# SmartSwitchBoard-2x2LK.net
KiCad netlist of a schematic drawn in EAGLE
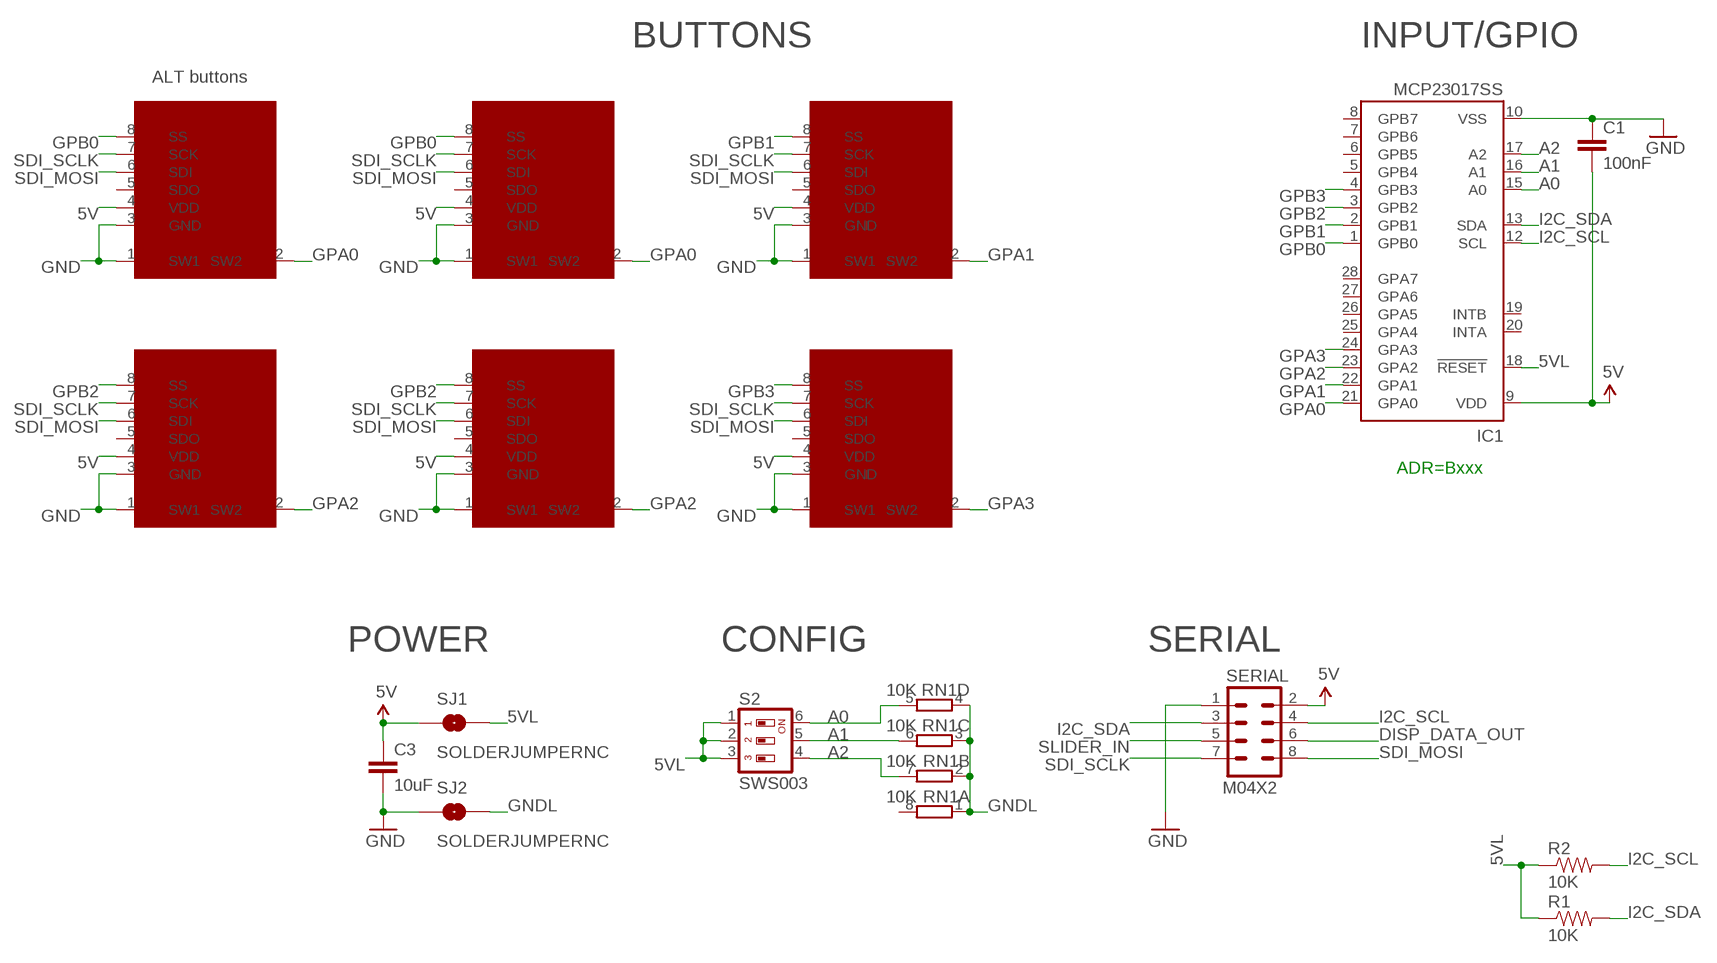
[diagram p0: schematic, sheet 1]

(export (version "E")
  (design (tool "Eeschema 10.0.6"))
  (components
    (comp (ref "C1")
      (value "100nF")
      (footprint "eagle-import:0603-CAP")
      (libsource (lib "eagle-import") (part "CAP0603-CAP"))
    )
    (comp (ref "C3")
      (value "10uF")
      (footprint "eagle-import:0805")
      (libsource (lib "eagle-import") (part "CAP0805"))
    )
    (comp (ref "IC1")
      (value "MCP23017SS")
      (footprint "eagle-import:SSOP28")
      (fields
        (field (name "MF") "MICROCHIP")
        (field (name "MPN") "MCP23017-E/SS")
        (field (name "MPN_1") "MCP23017-E/SS")
        (field (name "OC_FARNELL") "1467674")
        (field (name "OC_NEWARK") "31K2960")
      )
      (libsource (lib "eagle-import") (part "MCP23017SS"))
    )
    (comp (ref "R1")
      (value "10K")
      (footprint "eagle-import:0603-RES")
      (libsource (lib "eagle-import") (part "RESISTOR0603-RES"))
    )
    (comp (ref "R2")
      (value "10K")
      (footprint "eagle-import:0603-RES")
      (libsource (lib "eagle-import") (part "RESISTOR0603-RES"))
    )
    (comp (ref "RN1")
      (value "10K")
      (footprint "eagle-import:CAY16_HAND")
      (libsource (lib "eagle-import") (part "4R-NCAY16"))
    )
    (comp (ref "S2")
      (value "SWS003")
      (footprint "eagle-import:SMS-003")
      (libsource (lib "eagle-import") (part "SWS003"))
    )
    (comp (ref "SERIAL")
      (value "M04X2")
      (footprint "eagle-import:2X4")
      (libsource (lib "eagle-import") (part "M04X2"))
    )
    (comp (ref "SJ1")
      (value "SOLDERJUMPERNC")
      (footprint "eagle-import:SJ_2S")
      (libsource (lib "eagle-import") (part "SOLDERJUMPERNC"))
    )
    (comp (ref "SJ2")
      (value "SOLDERJUMPERNC")
      (footprint "eagle-import:SJ_2S")
      (libsource (lib "eagle-import") (part "SOLDERJUMPERNC"))
    )
    (comp (ref "U$2")
      (value "SMART_SWITCHSMART_SWITCH_8PIN")
      (footprint "eagle-import:SMART_SWITCH")
      (libsource (lib "eagle-import") (part "SMART_SWITCHSMART_SWITCH_8PIN"))
    )
    (comp (ref "U$3")
      (value "SMART_SWITCHSMART_SWITCH_8PIN")
      (footprint "eagle-import:SMART_SWITCH")
      (libsource (lib "eagle-import") (part "SMART_SWITCHSMART_SWITCH_8PIN"))
    )
    (comp (ref "U$4")
      (value "SMART_SWITCHSMART_SWITCH_8PIN")
      (footprint "eagle-import:SMART_SWITCH")
      (libsource (lib "eagle-import") (part "SMART_SWITCHSMART_SWITCH_8PIN"))
    )
    (comp (ref "U$5")
      (value "SMART_SWITCHSMART_SWITCH_8PIN")
      (footprint "eagle-import:SMART_SWITCH")
      (libsource (lib "eagle-import") (part "SMART_SWITCHSMART_SWITCH_8PIN"))
    )
    (comp (ref "U$6")
      (value "SMART_SWITCHSMART_SWITCH_8PIN")
      (footprint "eagle-import:SMART_SWITCH")
      (libsource (lib "eagle-import") (part "SMART_SWITCHSMART_SWITCH_8PIN"))
    )
    (comp (ref "U$7")
      (value "SMART_SWITCHSMART_SWITCH_8PIN")
      (footprint "eagle-import:SMART_SWITCH")
      (libsource (lib "eagle-import") (part "SMART_SWITCHSMART_SWITCH_8PIN"))
    )
  )
  (nets
    (net (code "1") (name "/5VL") (class "Default")
      (node (ref "IC1") (pin "18") (pinfunction "~{RESET}_18") (pintype "input"))
      (node (ref "R1") (pin "1") (pinfunction "1_1") (pintype "passive"))
      (node (ref "R2") (pin "1") (pinfunction "1_1") (pintype "passive"))
      (node (ref "S2") (pin "1") (pinfunction "1_1") (pintype "passive"))
      (node (ref "S2") (pin "2") (pinfunction "2_2") (pintype "passive"))
      (node (ref "S2") (pin "3") (pinfunction "3_3") (pintype "passive"))
      (node (ref "SJ1") (pin "2") (pinfunction "2_2") (pintype "passive"))
    )
    (net (code "2") (name "/A0") (class "Default")
      (node (ref "IC1") (pin "15") (pinfunction "A0_15") (pintype "input"))
      (node (ref "RN1") (pin "5") (pinfunction "2_5") (pintype "passive"))
      (node (ref "S2") (pin "6") (pinfunction "6_6") (pintype "passive"))
    )
    (net (code "3") (name "/A1") (class "Default")
      (node (ref "IC1") (pin "16") (pinfunction "A1_16") (pintype "input"))
      (node (ref "RN1") (pin "6") (pinfunction "2_6") (pintype "passive"))
      (node (ref "S2") (pin "5") (pinfunction "5_5") (pintype "passive"))
    )
    (net (code "4") (name "/A2") (class "Default")
      (node (ref "IC1") (pin "17") (pinfunction "A2_17") (pintype "input"))
      (node (ref "RN1") (pin "7") (pinfunction "2_7") (pintype "passive"))
      (node (ref "S2") (pin "4") (pinfunction "4_4") (pintype "passive"))
    )
    (net (code "5") (name "/DISP_DATA_OUT") (class "Default")
      (node (ref "SERIAL") (pin "6") (pinfunction "6_6") (pintype "passive"))
    )
    (net (code "6") (name "/GNDL") (class "Default")
      (node (ref "RN1") (pin "1") (pinfunction "1_1") (pintype "passive"))
      (node (ref "RN1") (pin "2") (pinfunction "1_2") (pintype "passive"))
      (node (ref "RN1") (pin "3") (pinfunction "1_3") (pintype "passive"))
      (node (ref "RN1") (pin "4") (pinfunction "1_4") (pintype "passive"))
      (node (ref "SJ2") (pin "2") (pinfunction "2_2") (pintype "passive"))
    )
    (net (code "7") (name "/GPA0") (class "Default")
      (node (ref "IC1") (pin "21") (pinfunction "GPA0_21") (pintype "bidirectional"))
      (node (ref "U$2") (pin "2") (pinfunction "SW2_2") (pintype "bidirectional"))
      (node (ref "U$6") (pin "2") (pinfunction "SW2_2") (pintype "bidirectional"))
    )
    (net (code "8") (name "/GPA1") (class "Default")
      (node (ref "IC1") (pin "22") (pinfunction "GPA1_22") (pintype "bidirectional"))
      (node (ref "U$3") (pin "2") (pinfunction "SW2_2") (pintype "bidirectional"))
    )
    (net (code "9") (name "/GPA2") (class "Default")
      (node (ref "IC1") (pin "23") (pinfunction "GPA2_23") (pintype "bidirectional"))
      (node (ref "U$4") (pin "2") (pinfunction "SW2_2") (pintype "bidirectional"))
      (node (ref "U$7") (pin "2") (pinfunction "SW2_2") (pintype "bidirectional"))
    )
    (net (code "10") (name "/GPA3") (class "Default")
      (node (ref "IC1") (pin "24") (pinfunction "GPA3_24") (pintype "bidirectional"))
      (node (ref "U$5") (pin "2") (pinfunction "SW2_2") (pintype "bidirectional"))
    )
    (net (code "11") (name "/GPB0") (class "Default")
      (node (ref "IC1") (pin "1") (pinfunction "GPB0_1") (pintype "bidirectional"))
      (node (ref "U$2") (pin "8") (pinfunction "SS_8") (pintype "bidirectional"))
      (node (ref "U$6") (pin "8") (pinfunction "SS_8") (pintype "bidirectional"))
    )
    (net (code "12") (name "/GPB1") (class "Default")
      (node (ref "IC1") (pin "2") (pinfunction "GPB1_2") (pintype "bidirectional"))
      (node (ref "U$3") (pin "8") (pinfunction "SS_8") (pintype "bidirectional"))
    )
    (net (code "13") (name "/GPB2") (class "Default")
      (node (ref "IC1") (pin "3") (pinfunction "GPB2_3") (pintype "bidirectional"))
      (node (ref "U$4") (pin "8") (pinfunction "SS_8") (pintype "bidirectional"))
      (node (ref "U$7") (pin "8") (pinfunction "SS_8") (pintype "bidirectional"))
    )
    (net (code "14") (name "/GPB3") (class "Default")
      (node (ref "IC1") (pin "4") (pinfunction "GPB3_4") (pintype "bidirectional"))
      (node (ref "U$5") (pin "8") (pinfunction "SS_8") (pintype "bidirectional"))
    )
    (net (code "15") (name "/I2C_SCL") (class "Default")
      (node (ref "IC1") (pin "12") (pinfunction "SCL_12") (pintype "input"))
      (node (ref "R2") (pin "2") (pinfunction "2_2") (pintype "passive"))
      (node (ref "SERIAL") (pin "4") (pinfunction "4_4") (pintype "passive"))
    )
    (net (code "16") (name "/I2C_SDA") (class "Default")
      (node (ref "IC1") (pin "13") (pinfunction "SDA_13") (pintype "bidirectional"))
      (node (ref "R1") (pin "2") (pinfunction "2_2") (pintype "passive"))
      (node (ref "SERIAL") (pin "3") (pinfunction "3_3") (pintype "passive"))
    )
    (net (code "17") (name "/SDI_MOSI") (class "Default")
      (node (ref "SERIAL") (pin "8") (pinfunction "8_8") (pintype "passive"))
      (node (ref "U$2") (pin "6") (pinfunction "SDI_6") (pintype "bidirectional"))
      (node (ref "U$3") (pin "6") (pinfunction "SDI_6") (pintype "bidirectional"))
      (node (ref "U$4") (pin "6") (pinfunction "SDI_6") (pintype "bidirectional"))
      (node (ref "U$5") (pin "6") (pinfunction "SDI_6") (pintype "bidirectional"))
      (node (ref "U$6") (pin "6") (pinfunction "SDI_6") (pintype "bidirectional"))
      (node (ref "U$7") (pin "6") (pinfunction "SDI_6") (pintype "bidirectional"))
    )
    (net (code "18") (name "/SDI_SCLK") (class "Default")
      (node (ref "SERIAL") (pin "7") (pinfunction "7_7") (pintype "passive"))
      (node (ref "U$2") (pin "7") (pinfunction "SCK_7") (pintype "bidirectional"))
      (node (ref "U$3") (pin "7") (pinfunction "SCK_7") (pintype "bidirectional"))
      (node (ref "U$4") (pin "7") (pinfunction "SCK_7") (pintype "bidirectional"))
      (node (ref "U$5") (pin "7") (pinfunction "SCK_7") (pintype "bidirectional"))
      (node (ref "U$6") (pin "7") (pinfunction "SCK_7") (pintype "bidirectional"))
      (node (ref "U$7") (pin "7") (pinfunction "SCK_7") (pintype "bidirectional"))
    )
    (net (code "19") (name "/SLIDER_IN") (class "Default")
      (node (ref "SERIAL") (pin "5") (pinfunction "5_5") (pintype "passive"))
    )
    (net (code "20") (name "5V") (class "Default")
      (node (ref "C1") (pin "2") (pinfunction "2_2") (pintype "passive"))
      (node (ref "C3") (pin "1") (pinfunction "1_1") (pintype "passive"))
      (node (ref "IC1") (pin "9") (pinfunction "VDD_9") (pintype "power_in"))
      (node (ref "SERIAL") (pin "2") (pinfunction "2_2") (pintype "passive"))
      (node (ref "SJ1") (pin "1") (pinfunction "1_1") (pintype "passive"))
      (node (ref "U$2") (pin "4") (pinfunction "VDD_4") (pintype "bidirectional"))
      (node (ref "U$3") (pin "4") (pinfunction "VDD_4") (pintype "bidirectional"))
      (node (ref "U$4") (pin "4") (pinfunction "VDD_4") (pintype "bidirectional"))
      (node (ref "U$5") (pin "4") (pinfunction "VDD_4") (pintype "bidirectional"))
      (node (ref "U$6") (pin "4") (pinfunction "VDD_4") (pintype "bidirectional"))
      (node (ref "U$7") (pin "4") (pinfunction "VDD_4") (pintype "bidirectional"))
    )
    (net (code "21") (name "GND") (class "Default")
      (node (ref "C1") (pin "1") (pinfunction "1_1") (pintype "passive"))
      (node (ref "C3") (pin "2") (pinfunction "2_2") (pintype "passive"))
      (node (ref "IC1") (pin "10") (pinfunction "VSS_10") (pintype "power_in"))
      (node (ref "SERIAL") (pin "1") (pinfunction "1_1") (pintype "passive"))
      (node (ref "SJ2") (pin "1") (pinfunction "1_1") (pintype "passive"))
      (node (ref "U$2") (pin "1") (pinfunction "SW1_1") (pintype "bidirectional"))
      (node (ref "U$2") (pin "3") (pinfunction "GND_3") (pintype "bidirectional"))
      (node (ref "U$3") (pin "1") (pinfunction "SW1_1") (pintype "bidirectional"))
      (node (ref "U$3") (pin "3") (pinfunction "GND_3") (pintype "bidirectional"))
      (node (ref "U$4") (pin "1") (pinfunction "SW1_1") (pintype "bidirectional"))
      (node (ref "U$4") (pin "3") (pinfunction "GND_3") (pintype "bidirectional"))
      (node (ref "U$5") (pin "1") (pinfunction "SW1_1") (pintype "bidirectional"))
      (node (ref "U$5") (pin "3") (pinfunction "GND_3") (pintype "bidirectional"))
      (node (ref "U$6") (pin "1") (pinfunction "SW1_1") (pintype "bidirectional"))
      (node (ref "U$6") (pin "3") (pinfunction "GND_3") (pintype "bidirectional"))
      (node (ref "U$7") (pin "1") (pinfunction "SW1_1") (pintype "bidirectional"))
      (node (ref "U$7") (pin "3") (pinfunction "GND_3") (pintype "bidirectional"))
    )
    (net (code "22") (name "unconnected-(IC1-GPA4-Pad25)") (class "Default")
      (node (ref "IC1") (pin "25") (pinfunction "GPA4_25") (pintype "bidirectional"))
    )
    (net (code "23") (name "unconnected-(IC1-GPA5-Pad26)") (class "Default")
      (node (ref "IC1") (pin "26") (pinfunction "GPA5_26") (pintype "bidirectional"))
    )
    (net (code "24") (name "unconnected-(IC1-GPA6-Pad27)") (class "Default")
      (node (ref "IC1") (pin "27") (pinfunction "GPA6_27") (pintype "bidirectional"))
    )
    (net (code "25") (name "unconnected-(IC1-GPA7-Pad28)") (class "Default")
      (node (ref "IC1") (pin "28") (pinfunction "GPA7_28") (pintype "bidirectional"))
    )
    (net (code "26") (name "unconnected-(IC1-GPB4-Pad5)") (class "Default")
      (node (ref "IC1") (pin "5") (pinfunction "GPB4_5") (pintype "bidirectional"))
    )
    (net (code "27") (name "unconnected-(IC1-GPB5-Pad6)") (class "Default")
      (node (ref "IC1") (pin "6") (pinfunction "GPB5_6") (pintype "bidirectional"))
    )
    (net (code "28") (name "unconnected-(IC1-GPB6-Pad7)") (class "Default")
      (node (ref "IC1") (pin "7") (pinfunction "GPB6_7") (pintype "bidirectional"))
    )
    (net (code "29") (name "unconnected-(IC1-GPB7-Pad8)") (class "Default")
      (node (ref "IC1") (pin "8") (pinfunction "GPB7_8") (pintype "bidirectional"))
    )
    (net (code "30") (name "unconnected-(IC1-INTA-Pad20)") (class "Default")
      (node (ref "IC1") (pin "20") (pinfunction "INTA_20") (pintype "output"))
    )
    (net (code "31") (name "unconnected-(IC1-INTB-Pad19)") (class "Default")
      (node (ref "IC1") (pin "19") (pinfunction "INTB_19") (pintype "output"))
    )
    (net (code "32") (name "unconnected-(RN1A-2-Pad8)") (class "Default")
      (node (ref "RN1") (pin "8") (pinfunction "2_8") (pintype "passive"))
    )
    (net (code "33") (name "unconnected-(U$2-SDO-Pad5)") (class "Default")
      (node (ref "U$2") (pin "5") (pinfunction "SDO_5") (pintype "bidirectional"))
    )
    (net (code "34") (name "unconnected-(U$3-SDO-Pad5)") (class "Default")
      (node (ref "U$3") (pin "5") (pinfunction "SDO_5") (pintype "bidirectional"))
    )
    (net (code "35") (name "unconnected-(U$4-SDO-Pad5)") (class "Default")
      (node (ref "U$4") (pin "5") (pinfunction "SDO_5") (pintype "bidirectional"))
    )
    (net (code "36") (name "unconnected-(U$5-SDO-Pad5)") (class "Default")
      (node (ref "U$5") (pin "5") (pinfunction "SDO_5") (pintype "bidirectional"))
    )
    (net (code "37") (name "unconnected-(U$6-SDO-Pad5)") (class "Default")
      (node (ref "U$6") (pin "5") (pinfunction "SDO_5") (pintype "bidirectional"))
    )
    (net (code "38") (name "unconnected-(U$7-SDO-Pad5)") (class "Default")
      (node (ref "U$7") (pin "5") (pinfunction "SDO_5") (pintype "bidirectional"))
    )
  )
)
